# USBHub.net
KiCad netlist of a schematic drawn in Altium Designer
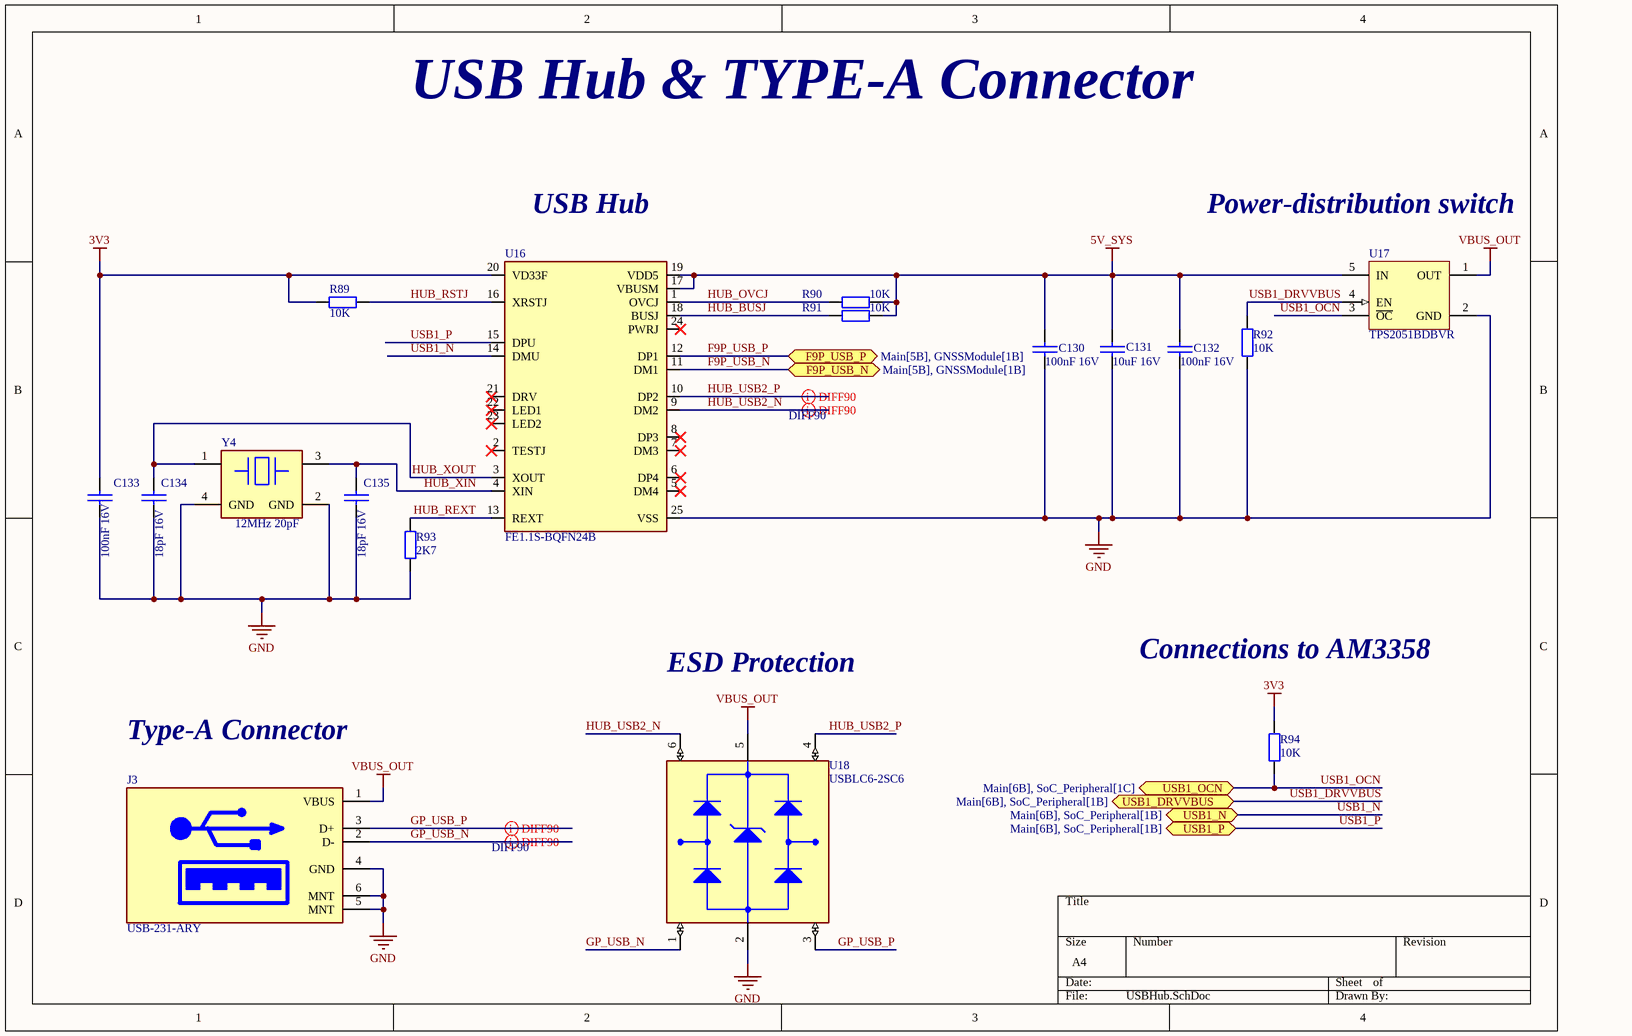
[diagram p0: USBHub.SchDoc]

(export (version "E")
  (design (tool "Eeschema 10.0.6"))
  (components
    (comp (ref "C130")
      (value "100nF 16V")
      (footprint "C_0402")
      (description "Capacitor 0402 SMD")
      (libsource (lib "tor1kkLib") (part "C_0402"))
    )
    (comp (ref "C131")
      (value "10uF 16V")
      (footprint "C_0603")
      (description "Capacitor 0603 SMD")
      (libsource (lib "tor1kkLib") (part "C_0603"))
    )
    (comp (ref "C132")
      (value "100nF 16V")
      (footprint "C_0402")
      (description "Capacitor 0402 SMD")
      (libsource (lib "tor1kkLib") (part "C_0402"))
    )
    (comp (ref "C133")
      (value "100nF 16V")
      (footprint "C_0402")
      (description "Capacitor 0402 SMD")
      (libsource (lib "tor1kkLib") (part "C_0402"))
    )
    (comp (ref "C134")
      (value "18pF 16V")
      (footprint "C_0402")
      (description "Capacitor 0402 SMD")
      (libsource (lib "tor1kkLib") (part "C_0402"))
    )
    (comp (ref "C135")
      (value "18pF 16V")
      (footprint "C_0402")
      (description "Capacitor 0402 SMD")
      (libsource (lib "tor1kkLib") (part "C_0402"))
    )
    (comp (ref "J3")
      (value "USB-231-ARY")
      (footprint "TYPE-A_W14xD14.45xH7")
      (description "Type-A 1.5A USB 2.0 1 Bend-in 4P Female -20℃~+70℃  Plugin USB Connectors ROHS")
      (fields (field (name "MANUFACTURER") "XUNPU"))
      (libsource (lib "tor1kkLib") (part "USB-231-ARY"))
    )
    (comp (ref "R89")
      (value "10K")
      (footprint "R_0402")
      (description "Resistor 0402 SMD")
      (libsource (lib "tor1kkLib") (part "R_0402"))
    )
    (comp (ref "R90")
      (value "10K")
      (footprint "R_0402")
      (description "Resistor 0402 SMD")
      (libsource (lib "tor1kkLib") (part "R_0402"))
    )
    (comp (ref "R91")
      (value "10K")
      (footprint "R_0402")
      (description "Resistor 0402 SMD")
      (libsource (lib "tor1kkLib") (part "R_0402"))
    )
    (comp (ref "R92")
      (value "10K")
      (footprint "R_0402")
      (description "Resistor 0402 SMD")
      (libsource (lib "") (part "R_0402_2"))
    )
    (comp (ref "R93")
      (value "2K7")
      (footprint "R_0402")
      (description "Resistor 0402 SMD")
      (libsource (lib "") (part "R_0402_1"))
    )
    (comp (ref "R94")
      (value "10K")
      (footprint "R_0402")
      (description "Resistor 0402 SMD")
      (libsource (lib "") (part "R_0402_2"))
    )
    (comp (ref "U16")
      (value "FE1.1S-BQFN24B")
      (footprint "QFN50P400X400X80-25N-D")
      (description "USB 2.0 4-PORT HuB CONTROLlER")
      (fields (field (name "MANUFACTURER") "Terminus Tech"))
      (libsource (lib "tor1kkLib") (part "FE1.1S-BQFN24B"))
    )
    (comp (ref "U17")
      (value "TPS2051BDBVR")
      (footprint "DBV0005A_L")
      (fields (field (name "MANUFACTURER") "TexasInstruments"))
      (libsource (lib "Altium Content Vault") (part "TI-TPS2051BDBV5"))
    )
    (comp (ref "U18")
      (value "USBLC6-2SC6")
      (footprint "SOT-23-6")
      (description "6A 12V 150W 6V Unidirectional 5V SOT-23-6 ESD and Surge Protection (TVS/ESD) ROHS")
      (fields (field (name "MANUFACTURER") "STMicroelectronics"))
      (libsource (lib "tor1kkLib") (part "USBLC6-2SC6"))
    )
    (comp (ref "Y4")
      (value "12MHz 20pF")
      (footprint "CRYSTAL_SMD3225-4P")
      (description "12MHz Surface Mount Crystal 20pF ±10ppm ±20ppm SMD3225-4P Crystals ROHS")
      (fields
        (field (name "MANUFACTURER") "YXC Crystal Oscillators")
        (field (name "MANUFACTURER PART NUMBER") "X322512MSB4SI")
      )
      (libsource (lib "tor1kkLib") (part "X322512MSB4SI"))
    )
  )
  (nets
    (net (code "1") (name "/F9P_USB_N") (class "Default")
      (node (ref "U16") (pin "11") (pinfunction "DM1_11") (pintype "passive"))
    )
    (net (code "2") (name "/F9P_USB_P") (class "Default")
      (node (ref "U16") (pin "12") (pinfunction "DP1_12") (pintype "passive"))
    )
    (net (code "3") (name "/GP_USB_N") (class "Default")
      (node (ref "J3") (pin "2") (pinfunction "D-_2") (pintype "passive"))
      (node (ref "U18") (pin "1") (pinfunction "I/O1_IN_1") (pintype "bidirectional"))
    )
    (net (code "4") (name "/GP_USB_P") (class "Default")
      (node (ref "J3") (pin "3") (pinfunction "D+_3") (pintype "passive"))
      (node (ref "U18") (pin "3") (pinfunction "I/O2_IN_3") (pintype "bidirectional"))
    )
    (net (code "5") (name "/HUB_BUSJ") (class "Default")
      (node (ref "R91") (pin "2") (pintype "passive"))
      (node (ref "U16") (pin "18") (pinfunction "BUSJ_18") (pintype "passive"))
    )
    (net (code "6") (name "/HUB_OVCJ") (class "Default")
      (node (ref "R90") (pin "2") (pintype "passive"))
      (node (ref "U16") (pin "1") (pinfunction "OVCJ_1") (pintype "passive"))
    )
    (net (code "7") (name "/HUB_REXT") (class "Default")
      (node (ref "R93") (pin "2") (pintype "passive"))
      (node (ref "U16") (pin "13") (pinfunction "REXT_13") (pintype "passive"))
    )
    (net (code "8") (name "/HUB_RSTJ") (class "Default")
      (node (ref "R89") (pin "1") (pintype "passive"))
      (node (ref "U16") (pin "16") (pinfunction "XRSTJ_16") (pintype "passive"))
    )
    (net (code "9") (name "/HUB_USB2_N") (class "Default")
      (node (ref "U16") (pin "9") (pinfunction "DM2_9") (pintype "passive"))
      (node (ref "U18") (pin "6") (pinfunction "I/O1_OUT_6") (pintype "bidirectional"))
    )
    (net (code "10") (name "/HUB_USB2_P") (class "Default")
      (node (ref "U16") (pin "10") (pinfunction "DP2_10") (pintype "passive"))
      (node (ref "U18") (pin "4") (pinfunction "I/O2_OUT_4") (pintype "bidirectional"))
    )
    (net (code "11") (name "/HUB_XIN") (class "Default")
      (node (ref "C135") (pin "2") (pintype "passive"))
      (node (ref "U16") (pin "4") (pinfunction "XIN_4") (pintype "passive"))
      (node (ref "Y4") (pin "3") (pinfunction "CRYSTAL_2_3") (pintype "passive"))
    )
    (net (code "12") (name "/HUB_XOUT") (class "Default")
      (node (ref "C134") (pin "2") (pintype "passive"))
      (node (ref "U16") (pin "3") (pinfunction "XOUT_3") (pintype "passive"))
      (node (ref "Y4") (pin "1") (pinfunction "CRYSTAL_1_1") (pintype "passive"))
    )
    (net (code "13") (name "/USB1_DRVVBUS") (class "Default")
      (node (ref "R92") (pin "1") (pintype "passive"))
      (node (ref "U17") (pin "4") (pinfunction "EN_4") (pintype "input"))
    )
    (net (code "14") (name "/USB1_N") (class "Default")
      (node (ref "U16") (pin "14") (pinfunction "DMU_14") (pintype "passive"))
    )
    (net (code "15") (name "/USB1_OCN") (class "Default")
      (node (ref "R94") (pin "2") (pintype "passive"))
      (node (ref "U17") (pin "3") (pinfunction "~{OC}_3") (pintype "open_collector"))
    )
    (net (code "16") (name "/USB1_P") (class "Default")
      (node (ref "U16") (pin "15") (pinfunction "DPU_15") (pintype "passive"))
    )
    (net (code "17") (name "3V3") (class "Default")
      (node (ref "C133") (pin "1") (pintype "passive"))
      (node (ref "R89") (pin "2") (pintype "passive"))
      (node (ref "R94") (pin "1") (pintype "passive"))
      (node (ref "U16") (pin "20") (pinfunction "VD33F_20") (pintype "power_in"))
    )
    (net (code "18") (name "5V_SYS") (class "Default")
      (node (ref "C130") (pin "1") (pintype "passive"))
      (node (ref "C131") (pin "1") (pintype "passive"))
      (node (ref "C132") (pin "1") (pintype "passive"))
      (node (ref "R90") (pin "1") (pintype "passive"))
      (node (ref "R91") (pin "1") (pintype "passive"))
      (node (ref "U16") (pin "17") (pinfunction "VBUSM_17") (pintype "passive"))
      (node (ref "U16") (pin "19") (pinfunction "VDD5_19") (pintype "power_in"))
      (node (ref "U17") (pin "5") (pinfunction "IN_5") (pintype "power_in"))
    )
    (net (code "19") (name "GND") (class "Default")
      (node (ref "C130") (pin "2") (pintype "passive"))
      (node (ref "C131") (pin "2") (pintype "passive"))
      (node (ref "C132") (pin "2") (pintype "passive"))
      (node (ref "C133") (pin "2") (pintype "passive"))
      (node (ref "C134") (pin "1") (pintype "passive"))
      (node (ref "C135") (pin "1") (pintype "passive"))
      (node (ref "J3") (pin "4") (pinfunction "GND_4") (pintype "passive"))
      (node (ref "J3") (pin "5") (pinfunction "MNT_5") (pintype "passive"))
      (node (ref "J3") (pin "6") (pinfunction "MNT_6") (pintype "passive"))
      (node (ref "R92") (pin "2") (pintype "passive"))
      (node (ref "R93") (pin "1") (pintype "passive"))
      (node (ref "U16") (pin "25") (pinfunction "VSS_25") (pintype "power_in"))
      (node (ref "U17") (pin "2") (pinfunction "GND_2") (pintype "power_in"))
      (node (ref "U18") (pin "2") (pinfunction "GND_2") (pintype "power_in"))
      (node (ref "Y4") (pin "2") (pinfunction "GND_2") (pintype "passive"))
      (node (ref "Y4") (pin "4") (pinfunction "GND_4") (pintype "passive"))
    )
    (net (code "20") (name "VBUS_OUT") (class "Default")
      (node (ref "J3") (pin "1") (pinfunction "VBUS_1") (pintype "passive"))
      (node (ref "U17") (pin "1") (pinfunction "OUT_1") (pintype "power_in"))
      (node (ref "U18") (pin "5") (pinfunction "VBUS_5") (pintype "power_in"))
    )
    (net (code "21") (name "unconnected-(U16-DM3-Pad7)") (class "Default")
      (node (ref "U16") (pin "7") (pinfunction "DM3_7") (pintype "passive+no_connect"))
    )
    (net (code "22") (name "unconnected-(U16-DM4-Pad5)") (class "Default")
      (node (ref "U16") (pin "5") (pinfunction "DM4_5") (pintype "passive+no_connect"))
    )
    (net (code "23") (name "unconnected-(U16-DP3-Pad8)") (class "Default")
      (node (ref "U16") (pin "8") (pinfunction "DP3_8") (pintype "passive+no_connect"))
    )
    (net (code "24") (name "unconnected-(U16-DP4-Pad6)") (class "Default")
      (node (ref "U16") (pin "6") (pinfunction "DP4_6") (pintype "passive+no_connect"))
    )
    (net (code "25") (name "unconnected-(U16-DRV-Pad21)") (class "Default")
      (node (ref "U16") (pin "21") (pinfunction "DRV_21") (pintype "passive+no_connect"))
    )
    (net (code "26") (name "unconnected-(U16-LED1-Pad22)") (class "Default")
      (node (ref "U16") (pin "22") (pinfunction "LED1_22") (pintype "passive+no_connect"))
    )
    (net (code "27") (name "unconnected-(U16-LED2-Pad23)") (class "Default")
      (node (ref "U16") (pin "23") (pinfunction "LED2_23") (pintype "passive+no_connect"))
    )
    (net (code "28") (name "unconnected-(U16-PWRJ-Pad24)") (class "Default")
      (node (ref "U16") (pin "24") (pinfunction "PWRJ_24") (pintype "passive+no_connect"))
    )
    (net (code "29") (name "unconnected-(U16-TESTJ-Pad2)") (class "Default")
      (node (ref "U16") (pin "2") (pinfunction "TESTJ_2") (pintype "passive+no_connect"))
    )
  )
)
